# Callisto_LSOx10_v1p0.net
KiCad netlist of a schematic drawn in EAGLE
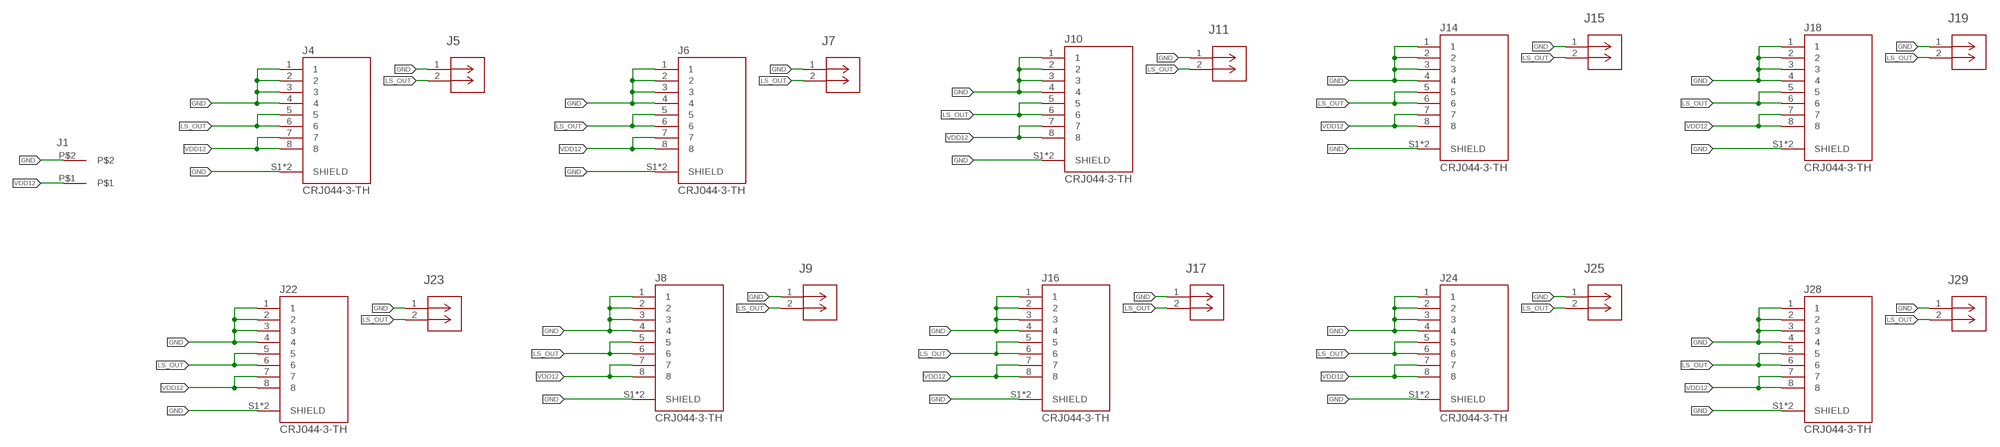
[diagram p0: schematic, sheet 1]

(export (version "E")
  (design (tool "Eeschema 10.0.6"))
  (components
    (comp (ref "J1")
      (value "2-pos")
      (footprint "eagle-import:2_3.81MM_PITCH")
      (fields (field (name "PARTNO") "691322310002"))
      (libsource (lib "eagle-import") (part "3.81MM_1_X_2_RT_ANGLE_PLUG_HEADER"))
    )
    (comp (ref "J4")
      (value "CRJ044-3-TH")
      (footprint "eagle-import:CUI_CRJ044-3-TH")
      (libsource (lib "eagle-import") (part "CRJ044-3-TH"))
    )
    (comp (ref "J5")
      (value "CONN_530470210_PICOBLADE_X_2")
      (footprint "eagle-import:CON_530470210_MOL")
      (fields
        (field (name "MANUFACTURER_PART_NUMBER") "530470210")
        (field (name "COPYRIGHT") "Copyright (C) 2022 Ultra Librarian. All rights reserved.")
      )
      (libsource (lib "eagle-import") (part "CONN_530470210_PICOBLADE_X_2"))
    )
    (comp (ref "J6")
      (value "CRJ044-3-TH")
      (footprint "eagle-import:CUI_CRJ044-3-TH")
      (libsource (lib "eagle-import") (part "CRJ044-3-TH"))
    )
    (comp (ref "J7")
      (value "CONN_530470210_PICOBLADE_X_2")
      (footprint "eagle-import:CON_530470210_MOL")
      (fields
        (field (name "MANUFACTURER_PART_NUMBER") "530470210")
        (field (name "COPYRIGHT") "Copyright (C) 2022 Ultra Librarian. All rights reserved.")
      )
      (libsource (lib "eagle-import") (part "CONN_530470210_PICOBLADE_X_2"))
    )
    (comp (ref "J8")
      (value "CRJ044-3-TH")
      (footprint "eagle-import:CUI_CRJ044-3-TH")
      (libsource (lib "eagle-import") (part "CRJ044-3-TH"))
    )
    (comp (ref "J9")
      (value "CONN_530470210_PICOBLADE_X_2")
      (footprint "eagle-import:CON_530470210_MOL")
      (fields
        (field (name "MANUFACTURER_PART_NUMBER") "530470210")
        (field (name "COPYRIGHT") "Copyright (C) 2022 Ultra Librarian. All rights reserved.")
      )
      (libsource (lib "eagle-import") (part "CONN_530470210_PICOBLADE_X_2"))
    )
    (comp (ref "J10")
      (value "CRJ044-3-TH")
      (footprint "eagle-import:CUI_CRJ044-3-TH")
      (libsource (lib "eagle-import") (part "CRJ044-3-TH"))
    )
    (comp (ref "J11")
      (value "CONN_530470210_PICOBLADE_X_2")
      (footprint "eagle-import:CON_530470210_MOL")
      (fields
        (field (name "MANUFACTURER_PART_NUMBER") "530470210")
        (field (name "COPYRIGHT") "Copyright (C) 2022 Ultra Librarian. All rights reserved.")
      )
      (libsource (lib "eagle-import") (part "CONN_530470210_PICOBLADE_X_2"))
    )
    (comp (ref "J14")
      (value "CRJ044-3-TH")
      (footprint "eagle-import:CUI_CRJ044-3-TH")
      (libsource (lib "eagle-import") (part "CRJ044-3-TH"))
    )
    (comp (ref "J15")
      (value "CONN_530470210_PICOBLADE_X_2")
      (footprint "eagle-import:CON_530470210_MOL")
      (fields
        (field (name "MANUFACTURER_PART_NUMBER") "530470210")
        (field (name "COPYRIGHT") "Copyright (C) 2022 Ultra Librarian. All rights reserved.")
      )
      (libsource (lib "eagle-import") (part "CONN_530470210_PICOBLADE_X_2"))
    )
    (comp (ref "J16")
      (value "CRJ044-3-TH")
      (footprint "eagle-import:CUI_CRJ044-3-TH")
      (libsource (lib "eagle-import") (part "CRJ044-3-TH"))
    )
    (comp (ref "J17")
      (value "CONN_530470210_PICOBLADE_X_2")
      (footprint "eagle-import:CON_530470210_MOL")
      (fields
        (field (name "MANUFACTURER_PART_NUMBER") "530470210")
        (field (name "COPYRIGHT") "Copyright (C) 2022 Ultra Librarian. All rights reserved.")
      )
      (libsource (lib "eagle-import") (part "CONN_530470210_PICOBLADE_X_2"))
    )
    (comp (ref "J18")
      (value "CRJ044-3-TH")
      (footprint "eagle-import:CUI_CRJ044-3-TH")
      (libsource (lib "eagle-import") (part "CRJ044-3-TH"))
    )
    (comp (ref "J19")
      (value "CONN_530470210_PICOBLADE_X_2")
      (footprint "eagle-import:CON_530470210_MOL")
      (fields
        (field (name "MANUFACTURER_PART_NUMBER") "530470210")
        (field (name "COPYRIGHT") "Copyright (C) 2022 Ultra Librarian. All rights reserved.")
      )
      (libsource (lib "eagle-import") (part "CONN_530470210_PICOBLADE_X_2"))
    )
    (comp (ref "J22")
      (value "CRJ044-3-TH")
      (footprint "eagle-import:CUI_CRJ044-3-TH")
      (libsource (lib "eagle-import") (part "CRJ044-3-TH"))
    )
    (comp (ref "J23")
      (value "CONN_530470210_PICOBLADE_X_2")
      (footprint "eagle-import:CON_530470210_MOL")
      (fields
        (field (name "MANUFACTURER_PART_NUMBER") "530470210")
        (field (name "COPYRIGHT") "Copyright (C) 2022 Ultra Librarian. All rights reserved.")
      )
      (libsource (lib "eagle-import") (part "CONN_530470210_PICOBLADE_X_2"))
    )
    (comp (ref "J24")
      (value "CRJ044-3-TH")
      (footprint "eagle-import:CUI_CRJ044-3-TH")
      (libsource (lib "eagle-import") (part "CRJ044-3-TH"))
    )
    (comp (ref "J25")
      (value "CONN_530470210_PICOBLADE_X_2")
      (footprint "eagle-import:CON_530470210_MOL")
      (fields
        (field (name "MANUFACTURER_PART_NUMBER") "530470210")
        (field (name "COPYRIGHT") "Copyright (C) 2022 Ultra Librarian. All rights reserved.")
      )
      (libsource (lib "eagle-import") (part "CONN_530470210_PICOBLADE_X_2"))
    )
    (comp (ref "J28")
      (value "CRJ044-3-TH")
      (footprint "eagle-import:CUI_CRJ044-3-TH")
      (libsource (lib "eagle-import") (part "CRJ044-3-TH"))
    )
    (comp (ref "J29")
      (value "CONN_530470210_PICOBLADE_X_2")
      (footprint "eagle-import:CON_530470210_MOL")
      (fields
        (field (name "MANUFACTURER_PART_NUMBER") "530470210")
        (field (name "COPYRIGHT") "Copyright (C) 2022 Ultra Librarian. All rights reserved.")
      )
      (libsource (lib "eagle-import") (part "CONN_530470210_PICOBLADE_X_2"))
    )
  )
  (nets
    (net (code "1") (name "GND") (class "Default")
      (node (ref "J1") (pin "P$2") (pinfunction "P$2_P$2") (pintype "bidirectional"))
      (node (ref "J10") (pin "1") (pinfunction "1_1") (pintype "passive"))
      (node (ref "J10") (pin "2") (pinfunction "2_2") (pintype "passive"))
      (node (ref "J10") (pin "3") (pinfunction "3_3") (pintype "passive"))
      (node (ref "J10") (pin "4") (pinfunction "4_4") (pintype "passive"))
      (node (ref "J10") (pin "S1") (pinfunction "SHIELD_S1") (pintype "passive"))
      (node (ref "J10") (pin "S2") (pinfunction "SHIELD_S2") (pintype "passive"))
      (node (ref "J11") (pin "1") (pinfunction "1_1") (pintype "passive"))
      (node (ref "J14") (pin "1") (pinfunction "1_1") (pintype "passive"))
      (node (ref "J14") (pin "2") (pinfunction "2_2") (pintype "passive"))
      (node (ref "J14") (pin "3") (pinfunction "3_3") (pintype "passive"))
      (node (ref "J14") (pin "4") (pinfunction "4_4") (pintype "passive"))
      (node (ref "J14") (pin "S1") (pinfunction "SHIELD_S1") (pintype "passive"))
      (node (ref "J14") (pin "S2") (pinfunction "SHIELD_S2") (pintype "passive"))
      (node (ref "J15") (pin "1") (pinfunction "1_1") (pintype "passive"))
      (node (ref "J16") (pin "1") (pinfunction "1_1") (pintype "passive"))
      (node (ref "J16") (pin "2") (pinfunction "2_2") (pintype "passive"))
      (node (ref "J16") (pin "3") (pinfunction "3_3") (pintype "passive"))
      (node (ref "J16") (pin "4") (pinfunction "4_4") (pintype "passive"))
      (node (ref "J16") (pin "S1") (pinfunction "SHIELD_S1") (pintype "passive"))
      (node (ref "J16") (pin "S2") (pinfunction "SHIELD_S2") (pintype "passive"))
      (node (ref "J17") (pin "1") (pinfunction "1_1") (pintype "passive"))
      (node (ref "J18") (pin "1") (pinfunction "1_1") (pintype "passive"))
      (node (ref "J18") (pin "2") (pinfunction "2_2") (pintype "passive"))
      (node (ref "J18") (pin "3") (pinfunction "3_3") (pintype "passive"))
      (node (ref "J18") (pin "4") (pinfunction "4_4") (pintype "passive"))
      (node (ref "J18") (pin "S1") (pinfunction "SHIELD_S1") (pintype "passive"))
      (node (ref "J18") (pin "S2") (pinfunction "SHIELD_S2") (pintype "passive"))
      (node (ref "J19") (pin "1") (pinfunction "1_1") (pintype "passive"))
      (node (ref "J22") (pin "1") (pinfunction "1_1") (pintype "passive"))
      (node (ref "J22") (pin "2") (pinfunction "2_2") (pintype "passive"))
      (node (ref "J22") (pin "3") (pinfunction "3_3") (pintype "passive"))
      (node (ref "J22") (pin "4") (pinfunction "4_4") (pintype "passive"))
      (node (ref "J22") (pin "S1") (pinfunction "SHIELD_S1") (pintype "passive"))
      (node (ref "J22") (pin "S2") (pinfunction "SHIELD_S2") (pintype "passive"))
      (node (ref "J23") (pin "1") (pinfunction "1_1") (pintype "passive"))
      (node (ref "J24") (pin "1") (pinfunction "1_1") (pintype "passive"))
      (node (ref "J24") (pin "2") (pinfunction "2_2") (pintype "passive"))
      (node (ref "J24") (pin "3") (pinfunction "3_3") (pintype "passive"))
      (node (ref "J24") (pin "4") (pinfunction "4_4") (pintype "passive"))
      (node (ref "J24") (pin "S1") (pinfunction "SHIELD_S1") (pintype "passive"))
      (node (ref "J24") (pin "S2") (pinfunction "SHIELD_S2") (pintype "passive"))
      (node (ref "J25") (pin "1") (pinfunction "1_1") (pintype "passive"))
      (node (ref "J28") (pin "1") (pinfunction "1_1") (pintype "passive"))
      (node (ref "J28") (pin "2") (pinfunction "2_2") (pintype "passive"))
      (node (ref "J28") (pin "3") (pinfunction "3_3") (pintype "passive"))
      (node (ref "J28") (pin "4") (pinfunction "4_4") (pintype "passive"))
      (node (ref "J28") (pin "S1") (pinfunction "SHIELD_S1") (pintype "passive"))
      (node (ref "J28") (pin "S2") (pinfunction "SHIELD_S2") (pintype "passive"))
      (node (ref "J29") (pin "1") (pinfunction "1_1") (pintype "passive"))
      (node (ref "J4") (pin "1") (pinfunction "1_1") (pintype "passive"))
      (node (ref "J4") (pin "2") (pinfunction "2_2") (pintype "passive"))
      (node (ref "J4") (pin "3") (pinfunction "3_3") (pintype "passive"))
      (node (ref "J4") (pin "4") (pinfunction "4_4") (pintype "passive"))
      (node (ref "J4") (pin "S1") (pinfunction "SHIELD_S1") (pintype "passive"))
      (node (ref "J4") (pin "S2") (pinfunction "SHIELD_S2") (pintype "passive"))
      (node (ref "J5") (pin "1") (pinfunction "1_1") (pintype "passive"))
      (node (ref "J6") (pin "1") (pinfunction "1_1") (pintype "passive"))
      (node (ref "J6") (pin "2") (pinfunction "2_2") (pintype "passive"))
      (node (ref "J6") (pin "3") (pinfunction "3_3") (pintype "passive"))
      (node (ref "J6") (pin "4") (pinfunction "4_4") (pintype "passive"))
      (node (ref "J6") (pin "S1") (pinfunction "SHIELD_S1") (pintype "passive"))
      (node (ref "J6") (pin "S2") (pinfunction "SHIELD_S2") (pintype "passive"))
      (node (ref "J7") (pin "1") (pinfunction "1_1") (pintype "passive"))
      (node (ref "J8") (pin "1") (pinfunction "1_1") (pintype "passive"))
      (node (ref "J8") (pin "2") (pinfunction "2_2") (pintype "passive"))
      (node (ref "J8") (pin "3") (pinfunction "3_3") (pintype "passive"))
      (node (ref "J8") (pin "4") (pinfunction "4_4") (pintype "passive"))
      (node (ref "J8") (pin "S1") (pinfunction "SHIELD_S1") (pintype "passive"))
      (node (ref "J8") (pin "S2") (pinfunction "SHIELD_S2") (pintype "passive"))
      (node (ref "J9") (pin "1") (pinfunction "1_1") (pintype "passive"))
    )
    (net (code "2") (name "LS_OUT") (class "Default")
      (node (ref "J10") (pin "5") (pinfunction "5_5") (pintype "passive"))
      (node (ref "J10") (pin "6") (pinfunction "6_6") (pintype "passive"))
      (node (ref "J11") (pin "2") (pinfunction "2_2") (pintype "passive"))
      (node (ref "J14") (pin "5") (pinfunction "5_5") (pintype "passive"))
      (node (ref "J14") (pin "6") (pinfunction "6_6") (pintype "passive"))
      (node (ref "J15") (pin "2") (pinfunction "2_2") (pintype "passive"))
      (node (ref "J16") (pin "5") (pinfunction "5_5") (pintype "passive"))
      (node (ref "J16") (pin "6") (pinfunction "6_6") (pintype "passive"))
      (node (ref "J17") (pin "2") (pinfunction "2_2") (pintype "passive"))
      (node (ref "J18") (pin "5") (pinfunction "5_5") (pintype "passive"))
      (node (ref "J18") (pin "6") (pinfunction "6_6") (pintype "passive"))
      (node (ref "J19") (pin "2") (pinfunction "2_2") (pintype "passive"))
      (node (ref "J22") (pin "5") (pinfunction "5_5") (pintype "passive"))
      (node (ref "J22") (pin "6") (pinfunction "6_6") (pintype "passive"))
      (node (ref "J23") (pin "2") (pinfunction "2_2") (pintype "passive"))
      (node (ref "J24") (pin "5") (pinfunction "5_5") (pintype "passive"))
      (node (ref "J24") (pin "6") (pinfunction "6_6") (pintype "passive"))
      (node (ref "J25") (pin "2") (pinfunction "2_2") (pintype "passive"))
      (node (ref "J28") (pin "5") (pinfunction "5_5") (pintype "passive"))
      (node (ref "J28") (pin "6") (pinfunction "6_6") (pintype "passive"))
      (node (ref "J29") (pin "2") (pinfunction "2_2") (pintype "passive"))
      (node (ref "J4") (pin "5") (pinfunction "5_5") (pintype "passive"))
      (node (ref "J4") (pin "6") (pinfunction "6_6") (pintype "passive"))
      (node (ref "J5") (pin "2") (pinfunction "2_2") (pintype "passive"))
      (node (ref "J6") (pin "5") (pinfunction "5_5") (pintype "passive"))
      (node (ref "J6") (pin "6") (pinfunction "6_6") (pintype "passive"))
      (node (ref "J7") (pin "2") (pinfunction "2_2") (pintype "passive"))
      (node (ref "J8") (pin "5") (pinfunction "5_5") (pintype "passive"))
      (node (ref "J8") (pin "6") (pinfunction "6_6") (pintype "passive"))
      (node (ref "J9") (pin "2") (pinfunction "2_2") (pintype "passive"))
    )
    (net (code "3") (name "VDD12") (class "Default")
      (node (ref "J1") (pin "P$1") (pinfunction "P$1_P$1") (pintype "bidirectional"))
      (node (ref "J10") (pin "7") (pinfunction "7_7") (pintype "passive"))
      (node (ref "J10") (pin "8") (pinfunction "8_8") (pintype "passive"))
      (node (ref "J14") (pin "7") (pinfunction "7_7") (pintype "passive"))
      (node (ref "J14") (pin "8") (pinfunction "8_8") (pintype "passive"))
      (node (ref "J16") (pin "7") (pinfunction "7_7") (pintype "passive"))
      (node (ref "J16") (pin "8") (pinfunction "8_8") (pintype "passive"))
      (node (ref "J18") (pin "7") (pinfunction "7_7") (pintype "passive"))
      (node (ref "J18") (pin "8") (pinfunction "8_8") (pintype "passive"))
      (node (ref "J22") (pin "7") (pinfunction "7_7") (pintype "passive"))
      (node (ref "J22") (pin "8") (pinfunction "8_8") (pintype "passive"))
      (node (ref "J24") (pin "7") (pinfunction "7_7") (pintype "passive"))
      (node (ref "J24") (pin "8") (pinfunction "8_8") (pintype "passive"))
      (node (ref "J28") (pin "7") (pinfunction "7_7") (pintype "passive"))
      (node (ref "J28") (pin "8") (pinfunction "8_8") (pintype "passive"))
      (node (ref "J4") (pin "7") (pinfunction "7_7") (pintype "passive"))
      (node (ref "J4") (pin "8") (pinfunction "8_8") (pintype "passive"))
      (node (ref "J6") (pin "7") (pinfunction "7_7") (pintype "passive"))
      (node (ref "J6") (pin "8") (pinfunction "8_8") (pintype "passive"))
      (node (ref "J8") (pin "7") (pinfunction "7_7") (pintype "passive"))
      (node (ref "J8") (pin "8") (pinfunction "8_8") (pintype "passive"))
    )
  )
)
